# transducer.net
KiCad netlist of a schematic drawn in EAGLE
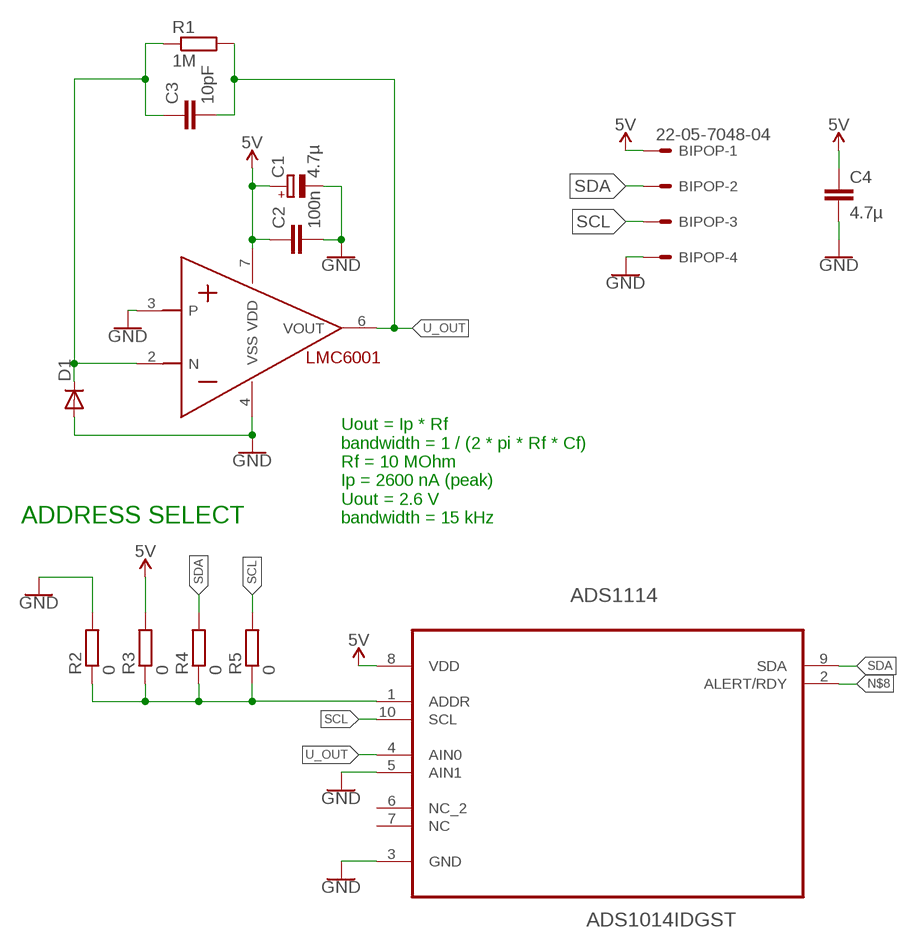
[diagram p0: schematic, sheet 1]

(export (version "E")
  (design (tool "Eeschema 10.0.6"))
  (components
    (comp (ref "ADS1114")
      (value "ADS1014IDGST")
      (footprint "eagle-import:SOP50P490X110-10N")
      (libsource (lib "eagle-import") (part "ADS1014IDGST"))
    )
    (comp (ref "BIPOP")
      (value "22-05-7048-04")
      (footprint "eagle-import:7395-04")
      (libsource (lib "eagle-import") (part "22-?-0405-7048"))
    )
    (comp (ref "C1")
      (value "4.7µ")
      (footprint "eagle-import:A_3216-18R")
      (libsource (lib "eagle-import") (part "CPOL-EUA/3216-18R"))
    )
    (comp (ref "C2")
      (value "100n")
      (footprint "eagle-import:C0805")
      (libsource (lib "eagle-import") (part "resistor_348_C-EUC0805"))
    )
    (comp (ref "C3")
      (value "10pF")
      (footprint "eagle-import:C0603")
      (libsource (lib "eagle-import") (part "C-EUC0603"))
    )
    (comp (ref "C4")
      (value "4.7µ")
      (footprint "eagle-import:C0805")
      (libsource (lib "eagle-import") (part "C-EUC0805"))
    )
    (comp (ref "D1")
      (value "DIODE-TO18D")
      (footprint "eagle-import:TO18D")
      (libsource (lib "eagle-import") (part "DIODE-TO18D"))
    )
    (comp (ref "LMC6001")
      (value "LMC6001")
      (footprint "eagle-import:DIL08")
      (libsource (lib "eagle-import") (part "LMC6001"))
    )
    (comp (ref "R1")
      (value "1M")
      (footprint "eagle-import:R0805")
      (libsource (lib "eagle-import") (part "R-EU_R0805"))
    )
    (comp (ref "R2")
      (value "0")
      (footprint "eagle-import:R0805")
      (libsource (lib "eagle-import") (part "R-EU_R0805"))
    )
    (comp (ref "R3")
      (value "0")
      (footprint "eagle-import:R0805")
      (libsource (lib "eagle-import") (part "R-EU_R0805"))
    )
    (comp (ref "R4")
      (value "0")
      (footprint "eagle-import:R0805")
      (libsource (lib "eagle-import") (part "R-EU_R0805"))
    )
    (comp (ref "R5")
      (value "0")
      (footprint "eagle-import:R0805")
      (libsource (lib "eagle-import") (part "R-EU_R0805"))
    )
  )
  (nets
    (net (code "1") (name "5V") (class "Default")
      (node (ref "ADS1114") (pin "8") (pinfunction "VDD_8") (pintype "power_in"))
      (node (ref "BIPOP") (pin "1") (pinfunction "S_1") (pintype "passive"))
      (node (ref "C1") (pin "+") (pinfunction "+_+") (pintype "passive"))
      (node (ref "C2") (pin "1") (pinfunction "1_1") (pintype "passive"))
      (node (ref "C4") (pin "1") (pinfunction "1_1") (pintype "passive"))
      (node (ref "LMC6001") (pin "7") (pinfunction "VDD_7") (pintype "power_in"))
      (node (ref "R3") (pin "2") (pinfunction "2_2") (pintype "passive"))
    )
    (net (code "2") (name "GND") (class "Default")
      (node (ref "ADS1114") (pin "3") (pinfunction "GND_3") (pintype "passive"))
      (node (ref "ADS1114") (pin "5") (pinfunction "AIN1_5") (pintype "input"))
      (node (ref "BIPOP") (pin "4") (pinfunction "S_4") (pintype "passive"))
      (node (ref "C1") (pin "-") (pinfunction "-_-") (pintype "passive"))
      (node (ref "C2") (pin "2") (pinfunction "2_2") (pintype "passive"))
      (node (ref "C4") (pin "2") (pinfunction "2_2") (pintype "passive"))
      (node (ref "D1") (pin "A") (pinfunction "A_A") (pintype "passive"))
      (node (ref "LMC6001") (pin "3") (pinfunction "P_3") (pintype "bidirectional"))
      (node (ref "LMC6001") (pin "4") (pinfunction "VSS_4") (pintype "power_in"))
      (node (ref "R2") (pin "2") (pinfunction "2_2") (pintype "passive"))
    )
    (net (code "3") (name "N$8") (class "Default")
      (node (ref "ADS1114") (pin "2") (pinfunction "ALERT/RDY_2") (pintype "output"))
    )
    (net (code "4") (name "Net-(ADS1114-ADDR)") (class "Default")
      (node (ref "ADS1114") (pin "1") (pinfunction "ADDR_1") (pintype "input"))
      (node (ref "R2") (pin "1") (pinfunction "1_1") (pintype "passive"))
      (node (ref "R3") (pin "1") (pinfunction "1_1") (pintype "passive"))
      (node (ref "R4") (pin "1") (pinfunction "1_1") (pintype "passive"))
      (node (ref "R5") (pin "1") (pinfunction "1_1") (pintype "passive"))
    )
    (net (code "5") (name "Net-(LMC6001-N)") (class "Default")
      (node (ref "C3") (pin "1") (pinfunction "1_1") (pintype "passive"))
      (node (ref "D1") (pin "C") (pinfunction "C_C") (pintype "passive"))
      (node (ref "LMC6001") (pin "2") (pinfunction "N_2") (pintype "bidirectional"))
      (node (ref "R1") (pin "1") (pinfunction "1_1") (pintype "passive"))
    )
    (net (code "6") (name "SCL") (class "Default")
      (node (ref "ADS1114") (pin "10") (pinfunction "SCL_10") (pintype "input"))
      (node (ref "BIPOP") (pin "3") (pinfunction "S_3") (pintype "passive"))
      (node (ref "R5") (pin "2") (pinfunction "2_2") (pintype "passive"))
    )
    (net (code "7") (name "SDA") (class "Default")
      (node (ref "ADS1114") (pin "9") (pinfunction "SDA_9") (pintype "bidirectional"))
      (node (ref "BIPOP") (pin "2") (pinfunction "S_2") (pintype "passive"))
      (node (ref "R4") (pin "2") (pinfunction "2_2") (pintype "passive"))
    )
    (net (code "8") (name "U_OUT") (class "Default")
      (node (ref "ADS1114") (pin "4") (pinfunction "AIN0_4") (pintype "input"))
      (node (ref "C3") (pin "2") (pinfunction "2_2") (pintype "passive"))
      (node (ref "LMC6001") (pin "6") (pinfunction "VOUT_6") (pintype "bidirectional"))
      (node (ref "R1") (pin "2") (pinfunction "2_2") (pintype "passive"))
    )
    (net (code "9") (name "unconnected-(ADS1114-NC-Pad7)") (class "Default")
      (node (ref "ADS1114") (pin "7") (pinfunction "NC_7") (pintype "no_connect"))
    )
    (net (code "10") (name "unconnected-(ADS1114-NC_2-Pad6)") (class "Default")
      (node (ref "ADS1114") (pin "6") (pinfunction "NC_2_6") (pintype "no_connect"))
    )
  )
)
